# APP_UD.net
KiCad netlist of a schematic drawn in EAGLE
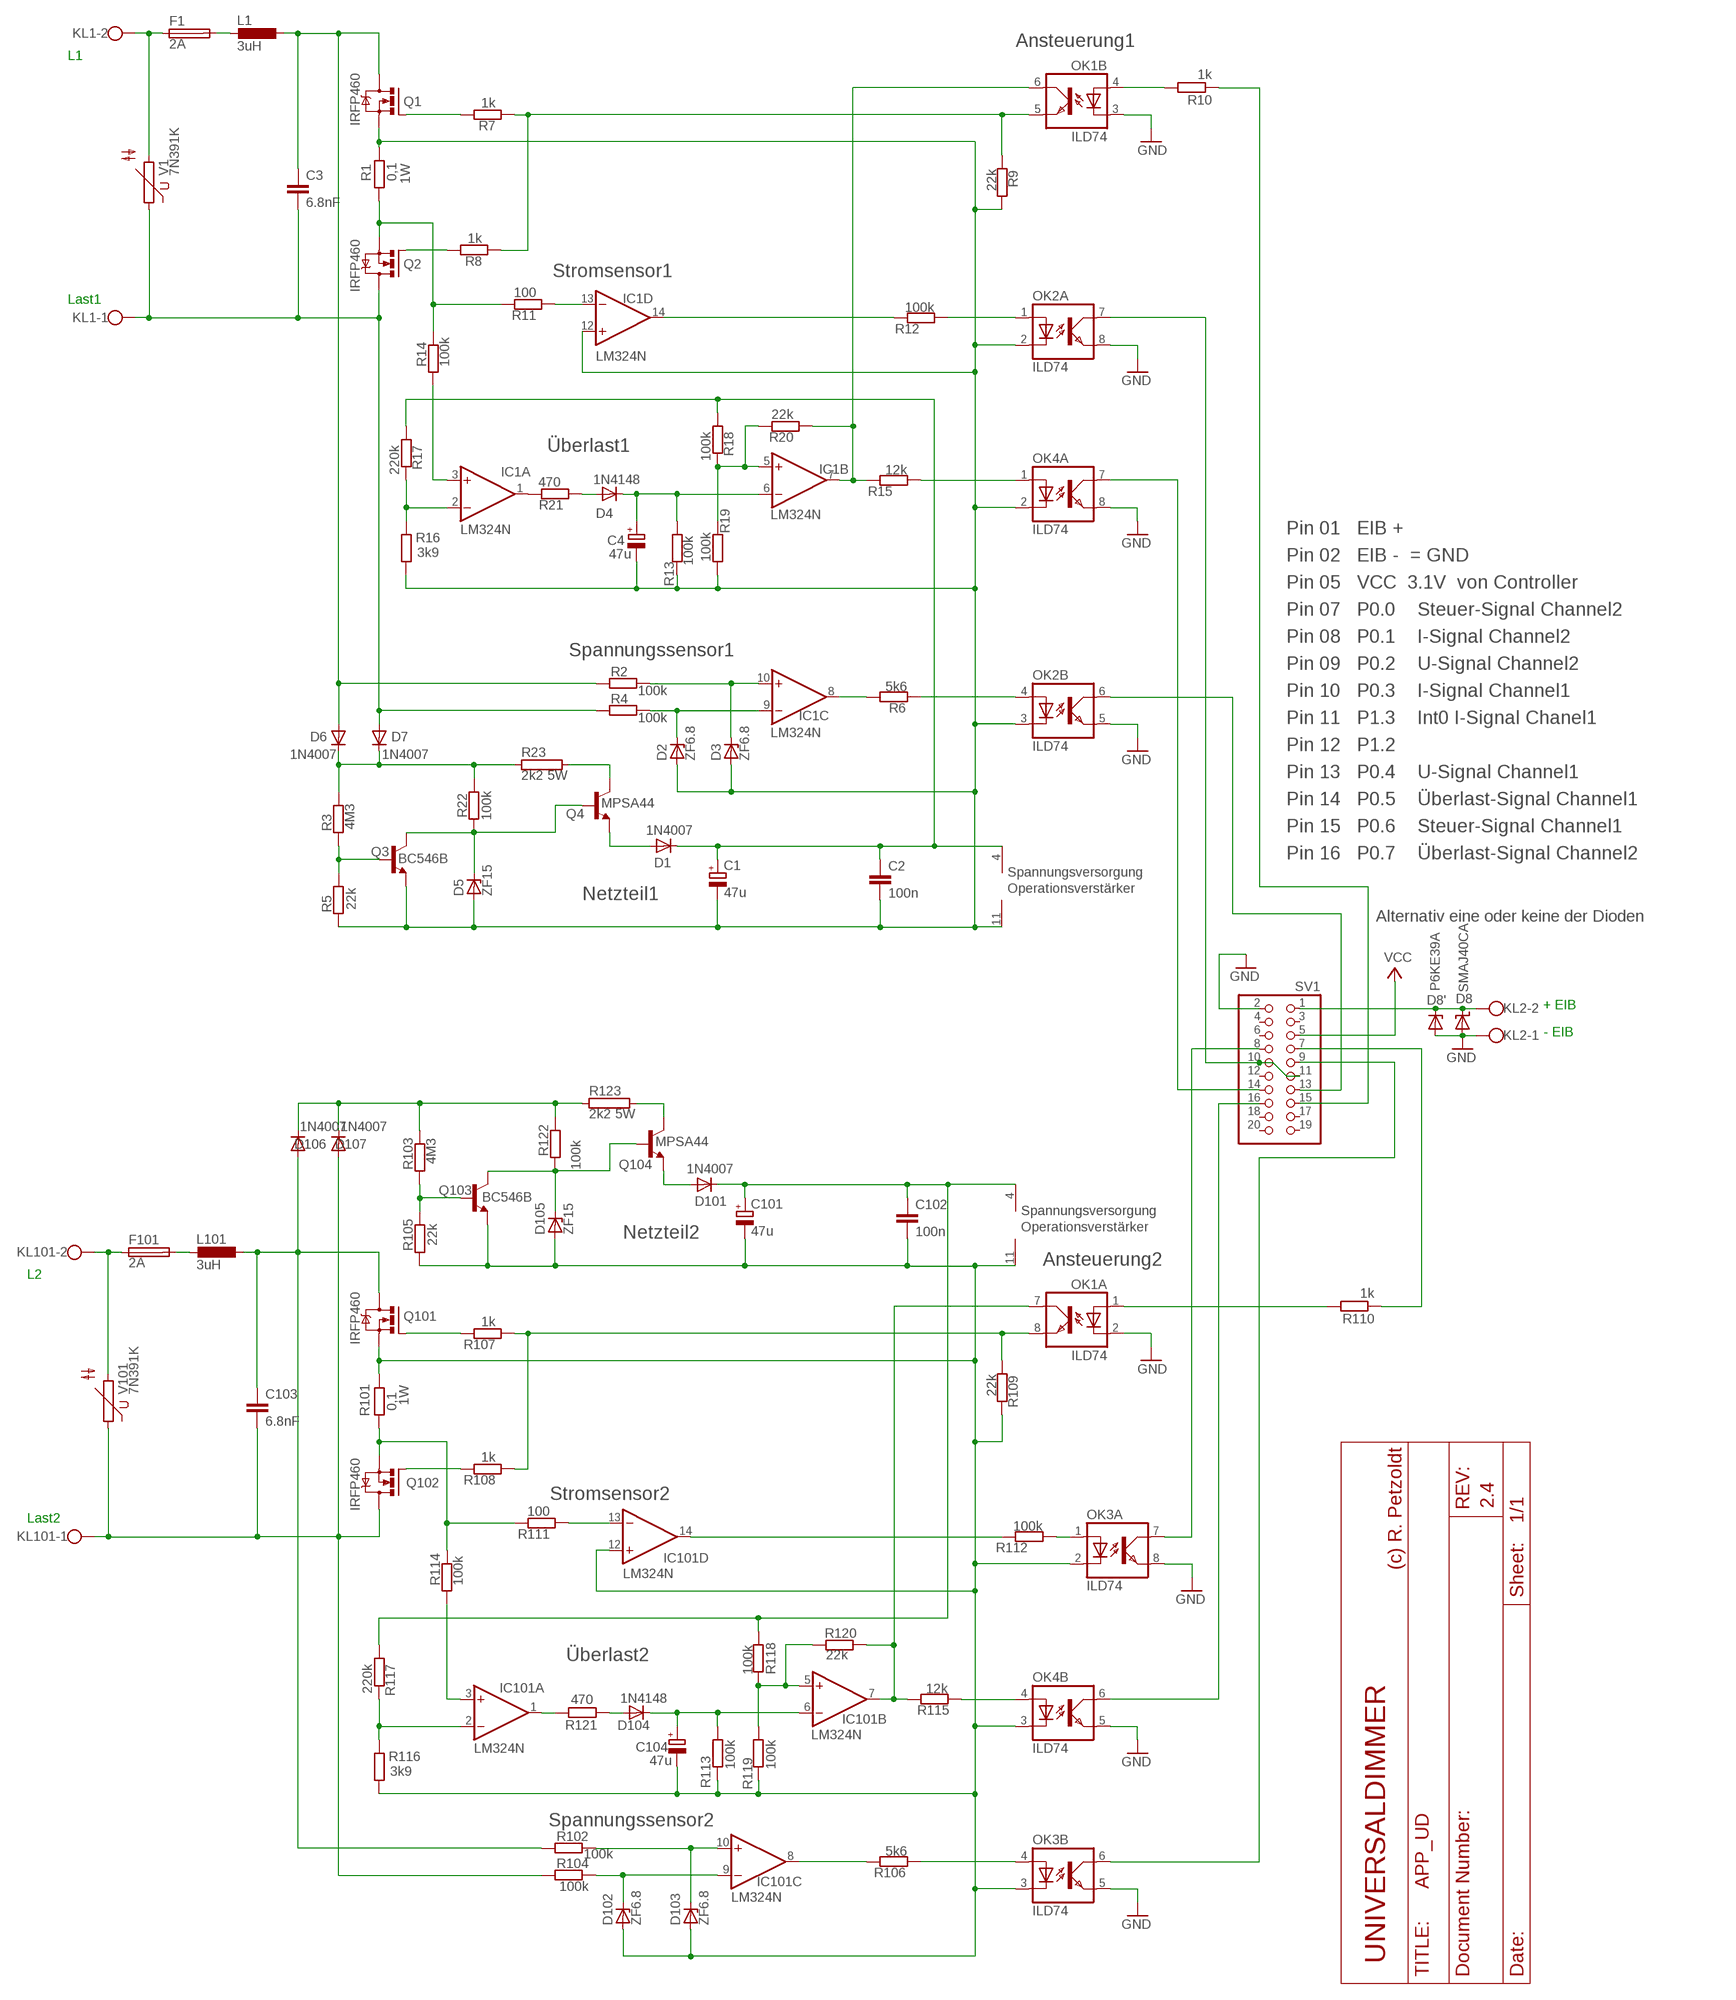
[diagram p0: schematic, sheet 1]

(export (version "E")
  (design (tool "Eeschema 10.0.6"))
  (components
    (comp (ref "C1")
      (value "47u")
      (footprint "eagle-import:E2-5")
      (libsource (lib "eagle-import") (part "CPOL-EUE2-5"))
    )
    (comp (ref "C2")
      (value "100n")
      (footprint "eagle-import:C025-030X050")
      (libsource (lib "eagle-import") (part "C-EU025-030X050"))
    )
    (comp (ref "C3")
      (value "6.8nF")
      (footprint "eagle-import:C050-075X075")
      (libsource (lib "eagle-import") (part "C-EU050-075X075"))
    )
    (comp (ref "C4")
      (value "47u")
      (footprint "eagle-import:E2-5")
      (libsource (lib "eagle-import") (part "CPOL-EUE2-5"))
    )
    (comp (ref "C101")
      (value "47u")
      (footprint "eagle-import:E2-5")
      (libsource (lib "eagle-import") (part "CPOL-EUE2-5"))
    )
    (comp (ref "C102")
      (value "100n")
      (footprint "eagle-import:C025-030X050")
      (libsource (lib "eagle-import") (part "C-EU025-030X050"))
    )
    (comp (ref "C103")
      (value "6.8nF")
      (footprint "eagle-import:C050-075X075")
      (libsource (lib "eagle-import") (part "C-EU050-075X075"))
    )
    (comp (ref "C104")
      (value "47u")
      (footprint "eagle-import:E2-5")
      (libsource (lib "eagle-import") (part "CPOL-EUE2-5"))
    )
    (comp (ref "D1")
      (value "1N4007")
      (footprint "eagle-import:D-7")
      (libsource (lib "eagle-import") (part "1N4148DO35-7S"))
    )
    (comp (ref "D2")
      (value "ZF6.8")
      (footprint "eagle-import:ZDIO-5")
      (libsource (lib "eagle-import") (part "ZENER-DIODEZD-5"))
    )
    (comp (ref "D3")
      (value "ZF6.8")
      (footprint "eagle-import:ZDIO-7.5")
      (libsource (lib "eagle-import") (part "ZENER-DIODEZD-7.5"))
    )
    (comp (ref "D4")
      (value "1N4148")
      (footprint "eagle-import:D-7")
      (libsource (lib "eagle-import") (part "1N4148DO35-7S"))
    )
    (comp (ref "D5")
      (value "ZF15")
      (footprint "eagle-import:ZDIO-7.5")
      (libsource (lib "eagle-import") (part "ZENER-DIODEZD-7.5"))
    )
    (comp (ref "D6")
      (value "1N4007")
      (footprint "eagle-import:D-7.5")
      (libsource (lib "eagle-import") (part "DIODE-D-7.5"))
    )
    (comp (ref "D7")
      (value "1N4007")
      (footprint "eagle-import:D-7.5")
      (libsource (lib "eagle-import") (part "DIODE-D-7.5"))
    )
    (comp (ref "D8")
      (value "SMAJ40CA")
      (footprint "eagle-import:SMBJ")
      (libsource (lib "eagle-import") (part "SUPPRESSOR-SMBJ"))
    )
    (comp (ref "D8'")
      (value "P6KE39A")
      (footprint "eagle-import:ZDIO-7.5")
      (libsource (lib "eagle-import") (part "ZENER-DIODEZD-7.5"))
    )
    (comp (ref "D101")
      (value "1N4007")
      (footprint "eagle-import:D-7")
      (libsource (lib "eagle-import") (part "1N4148DO35-7S"))
    )
    (comp (ref "D102")
      (value "ZF6.8")
      (footprint "eagle-import:ZDIO-5")
      (libsource (lib "eagle-import") (part "ZENER-DIODEZD-5"))
    )
    (comp (ref "D103")
      (value "ZF6.8")
      (footprint "eagle-import:ZDIO-7.5")
      (libsource (lib "eagle-import") (part "ZENER-DIODEZD-7.5"))
    )
    (comp (ref "D104")
      (value "1N4148")
      (footprint "eagle-import:D-7")
      (libsource (lib "eagle-import") (part "1N4148DO35-7S"))
    )
    (comp (ref "D105")
      (value "ZF15")
      (footprint "eagle-import:ZDIO-7.5")
      (libsource (lib "eagle-import") (part "ZENER-DIODEZD-7.5"))
    )
    (comp (ref "D106")
      (value "1N4007")
      (footprint "eagle-import:D-7.5")
      (libsource (lib "eagle-import") (part "DIODE-D-7.5"))
    )
    (comp (ref "D107")
      (value "1N4007")
      (footprint "eagle-import:D-7.5")
      (libsource (lib "eagle-import") (part "DIODE-D-7.5"))
    )
    (comp (ref "F1")
      (value "2A")
      (footprint "eagle-import:TR5")
      (libsource (lib "eagle-import") (part "TR5"))
    )
    (comp (ref "F101")
      (value "2A")
      (footprint "eagle-import:TR5")
      (libsource (lib "eagle-import") (part "TR5"))
    )
    (comp (ref "IC1")
      (value "LM324N")
      (footprint "eagle-import:DIL14")
      (libsource (lib "eagle-import") (part "LM324N"))
    )
    (comp (ref "IC101")
      (value "LM324N")
      (footprint "eagle-import:DIL14")
      (libsource (lib "eagle-import") (part "LM324N"))
    )
    (comp (ref "KL1")
      (value "W237-102")
      (footprint "eagle-import:W237-102")
      (libsource (lib "eagle-import") (part "W237-102"))
    )
    (comp (ref "KL2")
      (value "W237-102")
      (footprint "eagle-import:W237-102")
      (libsource (lib "eagle-import") (part "W237-102"))
    )
    (comp (ref "KL101")
      (value "W237-102")
      (footprint "eagle-import:W237-102")
      (libsource (lib "eagle-import") (part "W237-102"))
    )
    (comp (ref "L1")
      (value "3uH")
      (footprint "eagle-import:0414V")
      (libsource (lib "eagle-import") (part "L-EU414V"))
    )
    (comp (ref "L101")
      (value "3uH")
      (footprint "eagle-import:0414V")
      (libsource (lib "eagle-import") (part "L-EU414V"))
    )
    (comp (ref "OK1")
      (value "ILD74")
      (footprint "eagle-import:DIL08")
      (libsource (lib "eagle-import") (part "ILD2"))
    )
    (comp (ref "OK2")
      (value "ILD74")
      (footprint "eagle-import:DIL08")
      (libsource (lib "eagle-import") (part "ILD2"))
    )
    (comp (ref "OK3")
      (value "ILD74")
      (footprint "eagle-import:DIL08")
      (libsource (lib "eagle-import") (part "ILD2"))
    )
    (comp (ref "OK4")
      (value "ILD74")
      (footprint "eagle-import:DIL08")
      (libsource (lib "eagle-import") (part "ILD2"))
    )
    (comp (ref "Q1")
      (value "IRFP460")
      (footprint "eagle-import:TO247BV")
      (libsource (lib "eagle-import") (part "IRFPC40"))
    )
    (comp (ref "Q2")
      (value "IRFP460")
      (footprint "eagle-import:TO247BV")
      (libsource (lib "eagle-import") (part "IRFPC40"))
    )
    (comp (ref "Q3")
      (value "BC546B")
      (footprint "eagle-import:TO92-EBC")
      (libsource (lib "eagle-import") (part "BC546B"))
    )
    (comp (ref "Q4")
      (value "MPSA44")
      (footprint "eagle-import:TO92-EBC")
      (libsource (lib "eagle-import") (part "-NPN-TO92-EBCMPSA44"))
    )
    (comp (ref "Q101")
      (value "IRFP460")
      (footprint "eagle-import:TO247BV")
      (libsource (lib "eagle-import") (part "IRFPC40"))
    )
    (comp (ref "Q102")
      (value "IRFP460")
      (footprint "eagle-import:TO247BV")
      (libsource (lib "eagle-import") (part "IRFPC40"))
    )
    (comp (ref "Q103")
      (value "BC546B")
      (footprint "eagle-import:TO92-EBC")
      (libsource (lib "eagle-import") (part "BC546B"))
    )
    (comp (ref "Q104")
      (value "MPSA44")
      (footprint "eagle-import:TO92-EBC")
      (libsource (lib "eagle-import") (part "-NPN-TO92-EBCMPSA44"))
    )
    (comp (ref "R1")
      (value "0,1")
      (footprint "eagle-import:0414V")
      (libsource (lib "eagle-import") (part "R-EU_0414/5V"))
    )
    (comp (ref "R2")
      (value "100k")
      (footprint "eagle-import:0204_7")
      (libsource (lib "eagle-import") (part "R-EU_0204/7"))
    )
    (comp (ref "R3")
      (value "4M3")
      (footprint "eagle-import:0204_7")
      (libsource (lib "eagle-import") (part "R-EU_0204/7"))
    )
    (comp (ref "R4")
      (value "100k")
      (footprint "eagle-import:0204_7")
      (libsource (lib "eagle-import") (part "R-EU_0204/7"))
    )
    (comp (ref "R5")
      (value "22k")
      (footprint "eagle-import:0204_7")
      (libsource (lib "eagle-import") (part "R-EU_0204/7"))
    )
    (comp (ref "R6")
      (value "5k6")
      (footprint "eagle-import:0204_7")
      (libsource (lib "eagle-import") (part "R-EU_0204/7"))
    )
    (comp (ref "R7")
      (value "1k")
      (footprint "eagle-import:0204_7")
      (libsource (lib "eagle-import") (part "R-EU_0204/7"))
    )
    (comp (ref "R8")
      (value "1k")
      (footprint "eagle-import:0204_7")
      (libsource (lib "eagle-import") (part "R-EU_0204/7"))
    )
    (comp (ref "R9")
      (value "22k")
      (footprint "eagle-import:0204_7")
      (libsource (lib "eagle-import") (part "R-EU_0204/7"))
    )
    (comp (ref "R10")
      (value "1k")
      (footprint "eagle-import:0204_7")
      (libsource (lib "eagle-import") (part "R-EU_0204/7"))
    )
    (comp (ref "R11")
      (value "100")
      (footprint "eagle-import:0204_7")
      (libsource (lib "eagle-import") (part "R-EU_0204/7"))
    )
    (comp (ref "R12")
      (value "100k")
      (footprint "eagle-import:0204_7")
      (libsource (lib "eagle-import") (part "R-EU_0204/7"))
    )
    (comp (ref "R13")
      (value "100k")
      (footprint "eagle-import:0204_7")
      (libsource (lib "eagle-import") (part "R-EU_0204/7"))
    )
    (comp (ref "R14")
      (value "100k")
      (footprint "eagle-import:0204_7")
      (libsource (lib "eagle-import") (part "R-EU_0204/7"))
    )
    (comp (ref "R15")
      (value "12k")
      (footprint "eagle-import:0204_7")
      (libsource (lib "eagle-import") (part "R-EU_0204/7"))
    )
    (comp (ref "R16")
      (value "3k9")
      (footprint "eagle-import:0204_7")
      (libsource (lib "eagle-import") (part "R-EU_0204/7"))
    )
    (comp (ref "R17")
      (value "220k")
      (footprint "eagle-import:0204_7")
      (libsource (lib "eagle-import") (part "R-EU_0204/7"))
    )
    (comp (ref "R18")
      (value "100k")
      (footprint "eagle-import:0204_7")
      (libsource (lib "eagle-import") (part "R-EU_0204/7"))
    )
    (comp (ref "R19")
      (value "100k")
      (footprint "eagle-import:0204_7")
      (libsource (lib "eagle-import") (part "R-EU_0204/7"))
    )
    (comp (ref "R20")
      (value "22k")
      (footprint "eagle-import:0204_7")
      (libsource (lib "eagle-import") (part "R-EU_0204/7"))
    )
    (comp (ref "R21")
      (value "470")
      (footprint "eagle-import:0204_7")
      (libsource (lib "eagle-import") (part "R-EU_0204/7"))
    )
    (comp (ref "R22")
      (value "100k")
      (footprint "eagle-import:0204_7")
      (libsource (lib "eagle-import") (part "R-EU_0204/7"))
    )
    (comp (ref "R23")
      (value "2k2 5W")
      (footprint "eagle-import:KH208-8_10B")
      (libsource (lib "eagle-import") (part "R"))
    )
    (comp (ref "R101")
      (value "0,1")
      (footprint "eagle-import:0414V")
      (libsource (lib "eagle-import") (part "R-EU_0414/5V"))
    )
    (comp (ref "R102")
      (value "100k")
      (footprint "eagle-import:0204_7")
      (libsource (lib "eagle-import") (part "R-EU_0204/7"))
    )
    (comp (ref "R103")
      (value "4M3")
      (footprint "eagle-import:0204_7")
      (libsource (lib "eagle-import") (part "R-EU_0204/7"))
    )
    (comp (ref "R104")
      (value "100k")
      (footprint "eagle-import:0204_7")
      (libsource (lib "eagle-import") (part "R-EU_0204/7"))
    )
    (comp (ref "R105")
      (value "22k")
      (footprint "eagle-import:0204_7")
      (libsource (lib "eagle-import") (part "R-EU_0204/7"))
    )
    (comp (ref "R106")
      (value "5k6")
      (footprint "eagle-import:0204_7")
      (libsource (lib "eagle-import") (part "R-EU_0204/7"))
    )
    (comp (ref "R107")
      (value "1k")
      (footprint "eagle-import:0204_7")
      (libsource (lib "eagle-import") (part "R-EU_0204/7"))
    )
    (comp (ref "R108")
      (value "1k")
      (footprint "eagle-import:0204_7")
      (libsource (lib "eagle-import") (part "R-EU_0204/7"))
    )
    (comp (ref "R109")
      (value "22k")
      (footprint "eagle-import:0204_7")
      (libsource (lib "eagle-import") (part "R-EU_0204/7"))
    )
    (comp (ref "R110")
      (value "1k")
      (footprint "eagle-import:0204_7")
      (libsource (lib "eagle-import") (part "R-EU_0204/7"))
    )
    (comp (ref "R111")
      (value "100")
      (footprint "eagle-import:0204_7")
      (libsource (lib "eagle-import") (part "R-EU_0204/7"))
    )
    (comp (ref "R112")
      (value "100k")
      (footprint "eagle-import:0207_12")
      (libsource (lib "eagle-import") (part "R-EU_0207/12"))
    )
    (comp (ref "R113")
      (value "100k")
      (footprint "eagle-import:0204_7")
      (libsource (lib "eagle-import") (part "R-EU_0204/7"))
    )
    (comp (ref "R114")
      (value "100k")
      (footprint "eagle-import:0204_7")
      (libsource (lib "eagle-import") (part "R-EU_0204/7"))
    )
    (comp (ref "R115")
      (value "12k")
      (footprint "eagle-import:0204_7")
      (libsource (lib "eagle-import") (part "R-EU_0204/7"))
    )
    (comp (ref "R116")
      (value "3k9")
      (footprint "eagle-import:0204_7")
      (libsource (lib "eagle-import") (part "R-EU_0204/7"))
    )
    (comp (ref "R117")
      (value "220k")
      (footprint "eagle-import:0204_7")
      (libsource (lib "eagle-import") (part "R-EU_0204/7"))
    )
    (comp (ref "R118")
      (value "100k")
      (footprint "eagle-import:0204_7")
      (libsource (lib "eagle-import") (part "R-EU_0204/7"))
    )
    (comp (ref "R119")
      (value "100k")
      (footprint "eagle-import:0204_7")
      (libsource (lib "eagle-import") (part "R-EU_0204/7"))
    )
    (comp (ref "R120")
      (value "22k")
      (footprint "eagle-import:0204_7")
      (libsource (lib "eagle-import") (part "R-EU_0204/7"))
    )
    (comp (ref "R121")
      (value "470")
      (footprint "eagle-import:0204_7")
      (libsource (lib "eagle-import") (part "R-EU_0204/7"))
    )
    (comp (ref "R122")
      (value "100k")
      (footprint "eagle-import:0204_7")
      (libsource (lib "eagle-import") (part "R-EU_0204/7"))
    )
    (comp (ref "R123")
      (value "2k2 5W")
      (footprint "eagle-import:KH208-8_10B")
      (libsource (lib "eagle-import") (part "R"))
    )
    (comp (ref "SV1")
      (value "PINHD-2X10")
      (footprint "eagle-import:2X10")
      (libsource (lib "eagle-import") (part "PINHD-2X10"))
    )
    (comp (ref "V1")
      (value "7N391K")
      (footprint "eagle-import:S05K11")
      (libsource (lib "eagle-import") (part "S05K11"))
    )
    (comp (ref "V101")
      (value "7N391K")
      (footprint "eagle-import:S05K11")
      (libsource (lib "eagle-import") (part "S05K11"))
    )
  )
  (nets
    (net (code "1") (name "GND") (class "Default")
      (node (ref "D8") (pin "A") (pinfunction "A_A") (pintype "passive"))
      (node (ref "D8'") (pin "A") (pinfunction "A_A") (pintype "passive"))
      (node (ref "KL2") (pin "1") (pinfunction "KL_1") (pintype "passive"))
      (node (ref "OK1") (pin "2") (pinfunction "C_2") (pintype "passive"))
      (node (ref "OK1") (pin "3") (pinfunction "C_3") (pintype "passive"))
      (node (ref "OK2") (pin "5") (pinfunction "EMIT_5") (pintype "passive"))
      (node (ref "OK2") (pin "8") (pinfunction "EMIT_8") (pintype "passive"))
      (node (ref "OK3") (pin "5") (pinfunction "EMIT_5") (pintype "passive"))
      (node (ref "OK3") (pin "8") (pinfunction "EMIT_8") (pintype "passive"))
      (node (ref "OK4") (pin "5") (pinfunction "EMIT_5") (pintype "passive"))
      (node (ref "OK4") (pin "8") (pinfunction "EMIT_8") (pintype "passive"))
      (node (ref "SV1") (pin "2") (pinfunction "2_2") (pintype "passive"))
    )
    (net (code "2") (name "Net-(C3-Pad1)") (class "Default")
      (node (ref "C3") (pin "1") (pinfunction "1_1") (pintype "passive"))
      (node (ref "D6") (pin "A") (pinfunction "A_A") (pintype "passive"))
      (node (ref "L1") (pin "1") (pinfunction "1_1") (pintype "passive"))
      (node (ref "Q1") (pin "D") (pinfunction "D_D") (pintype "passive"))
      (node (ref "R2") (pin "1") (pinfunction "1_1") (pintype "passive"))
    )
    (net (code "3") (name "Net-(C103-Pad1)") (class "Default")
      (node (ref "C103") (pin "1") (pinfunction "1_1") (pintype "passive"))
      (node (ref "D106") (pin "A") (pinfunction "A_A") (pintype "passive"))
      (node (ref "L101") (pin "1") (pinfunction "1_1") (pintype "passive"))
      (node (ref "Q101") (pin "D") (pinfunction "D_D") (pintype "passive"))
      (node (ref "R102") (pin "1") (pinfunction "1_1") (pintype "passive"))
    )
    (net (code "4") (name "Net-(D1-PadA)") (class "Default")
      (node (ref "D1") (pin "A") (pinfunction "A_A") (pintype "passive"))
      (node (ref "Q4") (pin "E") (pinfunction "E_E") (pintype "passive"))
    )
    (net (code "5") (name "Net-(D4-PadA)") (class "Default")
      (node (ref "D4") (pin "A") (pinfunction "A_A") (pintype "passive"))
      (node (ref "R21") (pin "1") (pinfunction "1_1") (pintype "passive"))
    )
    (net (code "6") (name "Net-(D5-PadC)") (class "Default")
      (node (ref "D5") (pin "C") (pinfunction "C_C") (pintype "passive"))
      (node (ref "Q3") (pin "C") (pinfunction "C_C") (pintype "passive"))
      (node (ref "Q4") (pin "B") (pinfunction "B_B") (pintype "passive"))
      (node (ref "R22") (pin "1") (pinfunction "1_1") (pintype "passive"))
    )
    (net (code "7") (name "Net-(D101-PadA)") (class "Default")
      (node (ref "D101") (pin "A") (pinfunction "A_A") (pintype "passive"))
      (node (ref "Q104") (pin "E") (pinfunction "E_E") (pintype "passive"))
    )
    (net (code "8") (name "Net-(D104-PadA)") (class "Default")
      (node (ref "D104") (pin "A") (pinfunction "A_A") (pintype "passive"))
      (node (ref "R121") (pin "1") (pinfunction "1_1") (pintype "passive"))
    )
    (net (code "9") (name "Net-(D105-PadC)") (class "Default")
      (node (ref "D105") (pin "C") (pinfunction "C_C") (pintype "passive"))
      (node (ref "Q103") (pin "C") (pinfunction "C_C") (pintype "passive"))
      (node (ref "Q104") (pin "B") (pinfunction "B_B") (pintype "passive"))
      (node (ref "R122") (pin "1") (pinfunction "1_1") (pintype "passive"))
    )
    (net (code "10") (name "Net-(F1-Pad2)") (class "Default")
      (node (ref "F1") (pin "2") (pinfunction "2_2") (pintype "passive"))
      (node (ref "L1") (pin "2") (pinfunction "2_2") (pintype "passive"))
    )
    (net (code "11") (name "Net-(F101-Pad2)") (class "Default")
      (node (ref "F101") (pin "2") (pinfunction "2_2") (pintype "passive"))
      (node (ref "L101") (pin "2") (pinfunction "2_2") (pintype "passive"))
    )
    (net (code "12") (name "Net-(IC1A-+IN)") (class "Default")
      (node (ref "IC1") (pin "3") (pinfunction "+IN_3") (pintype "input"))
      (node (ref "R14") (pin "1") (pinfunction "1_1") (pintype "passive"))
    )
    (net (code "13") (name "Net-(IC1A--IN)") (class "Default")
      (node (ref "IC1") (pin "2") (pinfunction "-IN_2") (pintype "input"))
      (node (ref "R16") (pin "1") (pinfunction "1_1") (pintype "passive"))
      (node (ref "R17") (pin "2") (pinfunction "2_2") (pintype "passive"))
    )
    (net (code "14") (name "Net-(IC1A-OUT)") (class "Default")
      (node (ref "IC1") (pin "1") (pinfunction "OUT_1") (pintype "output"))
      (node (ref "R21") (pin "2") (pinfunction "2_2") (pintype "passive"))
    )
    (net (code "15") (name "Net-(IC1B-+IN)") (class "Default")
      (node (ref "IC1") (pin "5") (pinfunction "+IN_5") (pintype "input"))
      (node (ref "R18") (pin "2") (pinfunction "2_2") (pintype "passive"))
      (node (ref "R19") (pin "2") (pinfunction "2_2") (pintype "passive"))
      (node (ref "R20") (pin "2") (pinfunction "2_2") (pintype "passive"))
    )
    (net (code "16") (name "Net-(IC1B--IN)") (class "Default")
      (node (ref "C4") (pin "+") (pinfunction "+_+") (pintype "passive"))
      (node (ref "D4") (pin "C") (pinfunction "C_C") (pintype "passive"))
      (node (ref "IC1") (pin "6") (pinfunction "-IN_6") (pintype "input"))
      (node (ref "R13") (pin "1") (pinfunction "1_1") (pintype "passive"))
    )
    (net (code "17") (name "Net-(IC1B-OUT)") (class "Default")
      (node (ref "IC1") (pin "7") (pinfunction "OUT_7") (pintype "output"))
      (node (ref "OK1") (pin "6") (pinfunction "COL_6") (pintype "passive"))
      (node (ref "R15") (pin "2") (pinfunction "2_2") (pintype "passive"))
      (node (ref "R20") (pin "1") (pinfunction "1_1") (pintype "passive"))
    )
    (net (code "18") (name "Net-(IC1C-+IN)") (class "Default")
      (node (ref "D3") (pin "C") (pinfunction "C_C") (pintype "passive"))
      (node (ref "IC1") (pin "10") (pinfunction "+IN_10") (pintype "input"))
      (node (ref "R2") (pin "2") (pinfunction "2_2") (pintype "passive"))
    )
    (net (code "19") (name "Net-(IC1C--IN)") (class "Default")
      (node (ref "D2") (pin "C") (pinfunction "C_C") (pintype "passive"))
      (node (ref "IC1") (pin "9") (pinfunction "-IN_9") (pintype "input"))
      (node (ref "R4") (pin "2") (pinfunction "2_2") (pintype "passive"))
    )
    (net (code "20") (name "Net-(IC1C-OUT)") (class "Default")
      (node (ref "IC1") (pin "8") (pinfunction "OUT_8") (pintype "output"))
      (node (ref "R6") (pin "2") (pinfunction "2_2") (pintype "passive"))
    )
    (net (code "21") (name "Net-(IC1D-+IN)") (class "Default")
      (node (ref "C1") (pin "-") (pinfunction "-_-") (pintype "passive"))
      (node (ref "C2") (pin "2") (pinfunction "2_2") (pintype "passive"))
      (node (ref "C4") (pin "-") (pinfunction "-_-") (pintype "passive"))
      (node (ref "D2") (pin "A") (pinfunction "A_A") (pintype "passive"))
      (node (ref "D3") (pin "A") (pinfunction "A_A") (pintype "passive"))
      (node (ref "D5") (pin "A") (pinfunction "A_A") (pintype "passive"))
      (node (ref "IC1") (pin "11") (pinfunction "V-_11") (pintype "power_in"))
      (node (ref "IC1") (pin "12") (pinfunction "+IN_12") (pintype "input"))
      (node (ref "OK2") (pin "2") (pinfunction "C_2") (pintype "passive"))
      (node (ref "OK2") (pin "3") (pinfunction "C_3") (pintype "passive"))
      (node (ref "OK4") (pin "2") (pinfunction "C_2") (pintype "passive"))
      (node (ref "Q1") (pin "S") (pinfunction "S_S") (pintype "passive"))
      (node (ref "Q3") (pin "E") (pinfunction "E_E") (pintype "passive"))
      (node (ref "R1") (pin "2") (pinfunction "2_2") (pintype "passive"))
      (node (ref "R13") (pin "2") (pinfunction "2_2") (pintype "passive"))
      (node (ref "R16") (pin "2") (pinfunction "2_2") (pintype "passive"))
      (node (ref "R19") (pin "1") (pinfunction "1_1") (pintype "passive"))
      (node (ref "R5") (pin "1") (pinfunction "1_1") (pintype "passive"))
      (node (ref "R9") (pin "2") (pinfunction "2_2") (pintype "passive"))
    )
    (net (code "22") (name "Net-(IC1D--IN)") (class "Default")
      (node (ref "IC1") (pin "13") (pinfunction "-IN_13") (pintype "input"))
      (node (ref "R11") (pin "1") (pinfunction "1_1") (pintype "passive"))
    )
    (net (code "23") (name "Net-(IC1D-OUT)") (class "Default")
      (node (ref "IC1") (pin "14") (pinfunction "OUT_14") (pintype "output"))
      (node (ref "R12") (pin "2") (pinfunction "2_2") (pintype "passive"))
    )
    (net (code "24") (name "Net-(IC1E-V+)") (class "Default")
      (node (ref "C1") (pin "+") (pinfunction "+_+") (pintype "passive"))
      (node (ref "C2") (pin "1") (pinfunction "1_1") (pintype "passive"))
      (node (ref "D1") (pin "C") (pinfunction "C_C") (pintype "passive"))
      (node (ref "IC1") (pin "4") (pinfunction "V+_4") (pintype "power_in"))
      (node (ref "R17") (pin "1") (pinfunction "1_1") (pintype "passive"))
      (node (ref "R18") (pin "1") (pinfunction "1_1") (pintype "passive"))
    )
    (net (code "25") (name "Net-(IC101A-+IN)") (class "Default")
      (node (ref "IC101") (pin "3") (pinfunction "+IN_3") (pintype "input"))
      (node (ref "R114") (pin "1") (pinfunction "1_1") (pintype "passive"))
    )
    (net (code "26") (name "Net-(IC101A--IN)") (class "Default")
      (node (ref "IC101") (pin "2") (pinfunction "-IN_2") (pintype "input"))
      (node (ref "R116") (pin "1") (pinfunction "1_1") (pintype "passive"))
      (node (ref "R117") (pin "2") (pinfunction "2_2") (pintype "passive"))
    )
    (net (code "27") (name "Net-(IC101A-OUT)") (class "Default")
      (node (ref "IC101") (pin "1") (pinfunction "OUT_1") (pintype "output"))
      (node (ref "R121") (pin "2") (pinfunction "2_2") (pintype "passive"))
    )
    (net (code "28") (name "Net-(IC101B-+IN)") (class "Default")
      (node (ref "IC101") (pin "5") (pinfunction "+IN_5") (pintype "input"))
      (node (ref "R118") (pin "2") (pinfunction "2_2") (pintype "passive"))
      (node (ref "R119") (pin "1") (pinfunction "1_1") (pintype "passive"))
      (node (ref "R120") (pin "1") (pinfunction "1_1") (pintype "passive"))
    )
    (net (code "29") (name "Net-(IC101B--IN)") (class "Default")
      (node (ref "C104") (pin "+") (pinfunction "+_+") (pintype "passive"))
      (node (ref "D104") (pin "C") (pinfunction "C_C") (pintype "passive"))
      (node (ref "IC101") (pin "6") (pinfunction "-IN_6") (pintype "input"))
      (node (ref "R113") (pin "1") (pinfunction "1_1") (pintype "passive"))
    )
    (net (code "30") (name "Net-(IC101B-OUT)") (class "Default")
      (node (ref "IC101") (pin "7") (pinfunction "OUT_7") (pintype "output"))
      (node (ref "OK1") (pin "7") (pinfunction "COL_7") (pintype "passive"))
      (node (ref "R115") (pin "2") (pinfunction "2_2") (pintype "passive"))
      (node (ref "R120") (pin "2") (pinfunction "2_2") (pintype "passive"))
    )
    (net (code "31") (name "Net-(IC101C-+IN)") (class "Default")
      (node (ref "D103") (pin "C") (pinfunction "C_C") (pintype "passive"))
      (node (ref "IC101") (pin "10") (pinfunction "+IN_10") (pintype "input"))
      (node (ref "R102") (pin "2") (pinfunction "2_2") (pintype "passive"))
    )
    (net (code "32") (name "Net-(IC101C--IN)") (class "Default")
      (node (ref "D102") (pin "C") (pinfunction "C_C") (pintype "passive"))
      (node (ref "IC101") (pin "9") (pinfunction "-IN_9") (pintype "input"))
      (node (ref "R104") (pin "2") (pinfunction "2_2") (pintype "passive"))
    )
    (net (code "33") (name "Net-(IC101C-OUT)") (class "Default")
      (node (ref "IC101") (pin "8") (pinfunction "OUT_8") (pintype "output"))
      (node (ref "R106") (pin "2") (pinfunction "2_2") (pintype "passive"))
    )
    (net (code "34") (name "Net-(IC101D-+IN)") (class "Default")
      (node (ref "C101") (pin "-") (pinfunction "-_-") (pintype "passive"))
      (node (ref "C102") (pin "2") (pinfunction "2_2") (pintype "passive"))
      (node (ref "C104") (pin "-") (pinfunction "-_-") (pintype "passive"))
      (node (ref "D102") (pin "A") (pinfunction "A_A") (pintype "passive"))
      (node (ref "D103") (pin "A") (pinfunction "A_A") (pintype "passive"))
      (node (ref "D105") (pin "A") (pinfunction "A_A") (pintype "passive"))
      (node (ref "IC101") (pin "11") (pinfunction "V-_11") (pintype "power_in"))
      (node (ref "IC101") (pin "12") (pinfunction "+IN_12") (pintype "input"))
      (node (ref "OK3") (pin "2") (pinfunction "C_2") (pintype "passive"))
      (node (ref "OK3") (pin "3") (pinfunction "C_3") (pintype "passive"))
      (node (ref "OK4") (pin "3") (pinfunction "C_3") (pintype "passive"))
      (node (ref "Q101") (pin "S") (pinfunction "S_S") (pintype "passive"))
      (node (ref "Q103") (pin "E") (pinfunction "E_E") (pintype "passive"))
      (node (ref "R101") (pin "2") (pinfunction "2_2") (pintype "passive"))
      (node (ref "R105") (pin "1") (pinfunction "1_1") (pintype "passive"))
      (node (ref "R109") (pin "2") (pinfunction "2_2") (pintype "passive"))
      (node (ref "R113") (pin "2") (pinfunction "2_2") (pintype "passive"))
      (node (ref "R116") (pin "2") (pinfunction "2_2") (pintype "passive"))
      (node (ref "R119") (pin "2") (pinfunction "2_2") (pintype "passive"))
    )
    (net (code "35") (name "Net-(IC101D--IN)") (class "Default")
      (node (ref "IC101") (pin "13") (pinfunction "-IN_13") (pintype "input"))
      (node (ref "R111") (pin "1") (pinfunction "1_1") (pintype "passive"))
    )
    (net (code "36") (name "Net-(IC101D-OUT)") (class "Default")
      (node (ref "IC101") (pin "14") (pinfunction "OUT_14") (pintype "output"))
      (node (ref "R112") (pin "2") (pinfunction "2_2") (pintype "passive"))
    )
    (net (code "37") (name "Net-(IC101E-V+)") (class "Default")
      (node (ref "C101") (pin "+") (pinfunction "+_+") (pintype "passive"))
      (node (ref "C102") (pin "1") (pinfunction "1_1") (pintype "passive"))
      (node (ref "D101") (pin "C") (pinfunction "C_C") (pintype "passive"))
      (node (ref "IC101") (pin "4") (pinfunction "V+_4") (pintype "power_in"))
      (node (ref "R117") (pin "1") (pinfunction "1_1") (pintype "passive"))
      (node (ref "R118") (pin "1") (pinfunction "1_1") (pintype "passive"))
    )
    (net (code "38") (name "Net-(KL1A-KL)") (class "Default")
      (node (ref "C3") (pin "2") (pinfunction "2_2") (pintype "passive"))
      (node (ref "D7") (pin "A") (pinfunction "A_A") (pintype "passive"))
      (node (ref "KL1") (pin "1") (pinfunction "KL_1") (pintype "passive"))
      (node (ref "Q2") (pin "D") (pinfunction "D_D") (pintype "passive"))
      (node (ref "R4") (pin "1") (pinfunction "1_1") (pintype "passive"))
      (node (ref "V1") (pin "1") (pinfunction "1_1") (pintype "passive"))
    )
    (net (code "39") (name "Net-(KL1B-KL)") (class "Default")
      (node (ref "F1") (pin "1") (pinfunction "1_1") (pintype "passive"))
      (node (ref "KL1") (pin "2") (pinfunction "KL_2") (pintype "passive"))
      (node (ref "V1") (pin "2") (pinfunction "2_2") (pintype "passive"))
    )
    (net (code "40") (name "Net-(KL2B-KL)") (class "Default")
      (node (ref "D8") (pin "C") (pinfunction "C_C") (pintype "passive"))
      (node (ref "D8'") (pin "C") (pinfunction "C_C") (pintype "passive"))
      (node (ref "KL2") (pin "2") (pinfunction "KL_2") (pintype "passive"))
      (node (ref "SV1") (pin "1") (pinfunction "1_1") (pintype "passive"))
    )
    (net (code "41") (name "Net-(KL101A-KL)") (class "Default")
      (node (ref "C103") (pin "2") (pinfunction "2_2") (pintype "passive"))
      (node (ref "D107") (pin "A") (pinfunction "A_A") (pintype "passive"))
      (node (ref "KL101") (pin "1") (pinfunction "KL_1") (pintype "passive"))
      (node (ref "Q102") (pin "D") (pinfunction "D_D") (pintype "passive"))
      (node (ref "R104") (pin "1") (pinfunction "1_1") (pintype "passive"))
      (node (ref "V101") (pin "1") (pinfunction "1_1") (pintype "passive"))
    )
    (net (code "42") (name "Net-(KL101B-KL)") (class "Default")
      (node (ref "F101") (pin "1") (pinfunction "1_1") (pintype "passive"))
      (node (ref "KL101") (pin "2") (pinfunction "KL_2") (pintype "passive"))
      (node (ref "V101") (pin "2") (pinfunction "2_2") (pintype "passive"))
    )
    (net (code "43") (name "Net-(OK1A-A)") (class "Default")
      (node (ref "OK1") (pin "1") (pinfunction "A_1") (pintype "passive"))
      (node (ref "R110") (pin "2") (pinfunction "2_2") (pintype "passive"))
    )
    (net (code "44") (name "Net-(OK1A-EMIT)") (class "Default")
      (node (ref "OK1") (pin "8") (pinfunction "EMIT_8") (pintype "passive"))
      (node (ref "R107") (pin "1") (pinfunction "1_1") (pintype "passive"))
      (node (ref "R108") (pin "1") (pinfunction "1_1") (pintype "passive"))
      (node (ref "R109") (pin "1") (pinfunction "1_1") (pintype "passive"))
    )
    (net (code "45") (name "Net-(OK1B-A)") (class "Default")
      (node (ref "OK1") (pin "4") (pinfunction "A_4") (pintype "passive"))
      (node (ref "R10") (pin "2") (pinfunction "2_2") (pintype "passive"))
    )
    (net (code "46") (name "Net-(OK1B-EMIT)") (class "Default")
      (node (ref "OK1") (pin "5") (pinfunction "EMIT_5") (pintype "passive"))
      (node (ref "R7") (pin "1") (pinfunction "1_1") (pintype "passive"))
      (node (ref "R8") (pin "1") (pinfunction "1_1") (pintype "passive"))
      (node (ref "R9") (pin "1") (pinfunction "1_1") (pintype "passive"))
    )
    (net (code "47") (name "Net-(OK2A-A)") (class "Default")
      (node (ref "OK2") (pin "1") (pinfunction "A_1") (pintype "passive"))
      (node (ref "R12") (pin "1") (pinfunction "1_1") (pintype "passive"))
    )
    (net (code "48") (name "Net-(OK2A-COL)") (class "Default")
      (node (ref "OK2") (pin "7") (pinfunction "COL_7") (pintype "passive"))
      (node (ref "SV1") (pin "10") (pinfunction "10_10") (pintype "passive"))
      (node (ref "SV1") (pin "11") (pinfunction "11_11") (pintype "passive"))
    )
    (net (code "49") (name "Net-(OK2B-A)") (class "Default")
      (node (ref "OK2") (pin "4") (pinfunction "A_4") (pintype "passive"))
      (node (ref "R6") (pin "1") (pinfunction "1_1") (pintype "passive"))
    )
    (net (code "50") (name "Net-(OK2B-COL)") (class "Default")
      (node (ref "OK2") (pin "6") (pinfunction "COL_6") (pintype "passive"))
      (node (ref "SV1") (pin "13") (pinfunction "13_13") (pintype "passive"))
    )
    (net (code "51") (name "Net-(OK3A-A)") (class "Default")
      (node (ref "OK3") (pin "1") (pinfunction "A_1") (pintype "passive"))
      (node (ref "R112") (pin "1") (pinfunction "1_1") (pintype "passive"))
    )
    (net (code "52") (name "Net-(OK3A-COL)") (class "Default")
      (node (ref "OK3") (pin "7") (pinfunction "COL_7") (pintype "passive"))
      (node (ref "SV1") (pin "8") (pinfunction "8_8") (pintype "passive"))
    )
    (net (code "53") (name "Net-(OK3B-A)") (class "Default")
      (node (ref "OK3") (pin "4") (pinfunction "A_4") (pintype "passive"))
      (node (ref "R106") (pin "1") (pinfunction "1_1") (pintype "passive"))
    )
    (net (code "54") (name "Net-(OK3B-COL)") (class "Default")
      (node (ref "OK3") (pin "6") (pinfunction "COL_6") (pintype "passive"))
      (node (ref "SV1") (pin "9") (pinfunction "9_9") (pintype "passive"))
    )
    (net (code "55") (name "Net-(OK4A-A)") (class "Default")
      (node (ref "OK4") (pin "1") (pinfunction "A_1") (pintype "passive"))
      (node (ref "R15") (pin "1") (pinfunction "1_1") (pintype "passive"))
    )
    (net (code "56") (name "Net-(OK4A-COL)") (class "Default")
      (node (ref "OK4") (pin "7") (pinfunction "COL_7") (pintype "passive"))
      (node (ref "SV1") (pin "14") (pinfunction "14_14") (pintype "passive"))
    )
    (net (code "57") (name "Net-(OK4B-A)") (class "Default")
      (node (ref "OK4") (pin "4") (pinfunction "A_4") (pintype "passive"))
      (node (ref "R115") (pin "1") (pinfunction "1_1") (pintype "passive"))
    )
    (net (code "58") (name "Net-(OK4B-COL)") (class "Default")
      (node (ref "OK4") (pin "6") (pinfunction "COL_6") (pintype "passive"))
      (node (ref "SV1") (pin "16") (pinfunction "16_16") (pintype "passive"))
    )
    (net (code "59") (name "Net-(Q1-PadG)") (class "Default")
      (node (ref "Q1") (pin "G") (pinfunction "G_G") (pintype "passive"))
      (node (ref "R7") (pin "2") (pinfunction "2_2") (pintype "passive"))
    )
    (net (code "60") (name "Net-(Q2-PadG)") (class "Default")
      (node (ref "Q2") (pin "G") (pinfunction "G_G") (pintype "passive"))
      (node (ref "R8") (pin "2") (pinfunction "2_2") (pintype "passive"))
    )
    (net (code "61") (name "Net-(Q2-PadS)") (class "Default")
      (node (ref "Q2") (pin "S") (pinfunction "S_S") (pintype "passive"))
      (node (ref "R1") (pin "1") (pinfunction "1_1") (pintype "passive"))
      (node (ref "R11") (pin "2") (pinfunction "2_2") (pintype "passive"))
      (node (ref "R14") (pin "2") (pinfunction "2_2") (pintype "passive"))
    )
    (net (code "62") (name "Net-(Q3-PadB)") (class "Default")
      (node (ref "Q3") (pin "B") (pinfunction "B_B") (pintype "passive"))
      (node (ref "R3") (pin "1") (pinfunction "1_1") (pintype "passive"))
      (node (ref "R5") (pin "2") (pinfunction "2_2") (pintype "passive"))
    )
    (net (code "63") (name "Net-(Q101-PadG)") (class "Default")
      (node (ref "Q101") (pin "G") (pinfunction "G_G") (pintype "passive"))
      (node (ref "R107") (pin "2") (pinfunction "2_2") (pintype "passive"))
    )
    (net (code "64") (name "Net-(Q102-PadG)") (class "Default")
      (node (ref "Q102") (pin "G") (pinfunction "G_G") (pintype "passive"))
      (node (ref "R108") (pin "2") (pinfunction "2_2") (pintype "passive"))
    )
    (net (code "65") (name "Net-(Q102-PadS)") (class "Default")
      (node (ref "Q102") (pin "S") (pinfunction "S_S") (pintype "passive"))
      (node (ref "R101") (pin "1") (pinfunction "1_1") (pintype "passive"))
      (node (ref "R111") (pin "2") (pinfunction "2_2") (pintype "passive"))
      (node (ref "R114") (pin "2") (pinfunction "2_2") (pintype "passive"))
    )
    (net (code "66") (name "Net-(Q103-PadB)") (class "Default")
      (node (ref "Q103") (pin "B") (pinfunction "B_B") (pintype "passive"))
      (node (ref "R103") (pin "1") (pinfunction "1_1") (pintype "passive"))
      (node (ref "R105") (pin "2") (pinfunction "2_2") (pintype "passive"))
    )
    (net (code "67") (name "Net-(R10-Pad1)") (class "Default")
      (node (ref "R10") (pin "1") (pinfunction "1_1") (pintype "passive"))
      (node (ref "SV1") (pin "15") (pinfunction "15_15") (pintype "passive"))
    )
    (net (code "68") (name "Net-(R23-1)") (class "Default")
      (node (ref "D6") (pin "C") (pinfunction "C_C") (pintype "passive"))
      (node (ref "D7") (pin "C") (pinfunction "C_C") (pintype "passive"))
      (node (ref "R22") (pin "2") (pinfunction "2_2") (pintype "passive"))
      (node (ref "R23") (pin "P$1") (pinfunction "1_P$1") (pintype "passive"))
      (node (ref "R3") (pin "2") (pinfunction "2_2") (pintype "passive"))
    )
    (net (code "69") (name "Net-(R23-2)") (class "Default")
      (node (ref "Q4") (pin "C") (pinfunction "C_C") (pintype "passive"))
      (node (ref "R23") (pin "P$2") (pinfunction "2_P$2") (pintype "passive"))
    )
    (net (code "70") (name "Net-(R110-Pad1)") (class "Default")
      (node (ref "R110") (pin "1") (pinfunction "1_1") (pintype "passive"))
      (node (ref "SV1") (pin "7") (pinfunction "7_7") (pintype "passive"))
    )
    (net (code "71") (name "Net-(R123-1)") (class "Default")
      (node (ref "D106") (pin "C") (pinfunction "C_C") (pintype "passive"))
      (node (ref "D107") (pin "C") (pinfunction "C_C") (pintype "passive"))
      (node (ref "R103") (pin "2") (pinfunction "2_2") (pintype "passive"))
      (node (ref "R122") (pin "2") (pinfunction "2_2") (pintype "passive"))
      (node (ref "R123") (pin "P$1") (pinfunction "1_P$1") (pintype "passive"))
    )
    (net (code "72") (name "Net-(R123-2)") (class "Default")
      (node (ref "Q104") (pin "C") (pinfunction "C_C") (pintype "passive"))
      (node (ref "R123") (pin "P$2") (pinfunction "2_P$2") (pintype "passive"))
    )
    (net (code "73") (name "VCC") (class "Default")
      (node (ref "SV1") (pin "5") (pinfunction "5_5") (pintype "passive"))
    )
    (net (code "74") (name "unconnected-(SV1-Pad3)") (class "Default")
      (node (ref "SV1") (pin "3") (pinfunction "3_3") (pintype "passive"))
    )
    (net (code "75") (name "unconnected-(SV1-Pad4)") (class "Default")
      (node (ref "SV1") (pin "4") (pinfunction "4_4") (pintype "passive"))
    )
    (net (code "76") (name "unconnected-(SV1-Pad6)") (class "Default")
      (node (ref "SV1") (pin "6") (pinfunction "6_6") (pintype "passive"))
    )
    (net (code "77") (name "unconnected-(SV1-Pad12)") (class "Default")
      (node (ref "SV1") (pin "12") (pinfunction "12_12") (pintype "passive"))
    )
    (net (code "78") (name "unconnected-(SV1-Pad17)") (class "Default")
      (node (ref "SV1") (pin "17") (pinfunction "17_17") (pintype "passive"))
    )
    (net (code "79") (name "unconnected-(SV1-Pad18)") (class "Default")
      (node (ref "SV1") (pin "18") (pinfunction "18_18") (pintype "passive"))
    )
    (net (code "80") (name "unconnected-(SV1-Pad19)") (class "Default")
      (node (ref "SV1") (pin "19") (pinfunction "19_19") (pintype "passive"))
    )
    (net (code "81") (name "unconnected-(SV1-Pad20)") (class "Default")
      (node (ref "SV1") (pin "20") (pinfunction "20_20") (pintype "passive"))
    )
  )
)
